# Main.net
KiCad netlist of a schematic drawn in Altium Designer
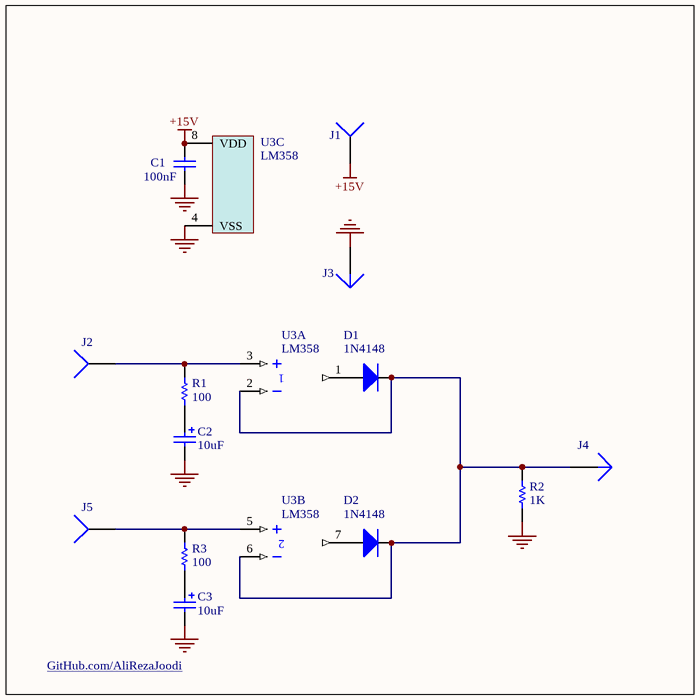
[diagram p0: Main.SchDoc]

(export (version "E")
  (design (tool "Eeschema 10.0.6"))
  (components
    (comp (ref "C1")
      (value "100nF")
      (footprint "CAPNTO2.54-3.05x1.78A")
      (description "Capacitor")
      (fields (field (name "MANUFACTURER") "Generic Components") (field (name "PUBLISHER") "Altium Limited"))
      (libsource (lib "Miscellaneous Devices") (part "Cap"))
    )
    (comp (ref "C2")
      (value "10uF")
      (footprint "CAPPR2.5-5x6")
      (description "Polarized Capacitor (Radial)")
      (fields (field (name "MANUFACTURER") "Generic Components") (field (name "PUBLISHER") "Altium Limited"))
      (libsource (lib "Miscellaneous Devices") (part "Cap Pol1"))
    )
    (comp (ref "C3")
      (value "10uF")
      (footprint "CAPPR2.5-5x6")
      (description "Polarized Capacitor (Radial)")
      (fields (field (name "MANUFACTURER") "Generic Components") (field (name "PUBLISHER") "Altium Limited"))
      (libsource (lib "Miscellaneous Devices") (part "Cap Pol1"))
    )
    (comp (ref "D1")
      (value "1N4148")
      (footprint "DIODE0.4_Glass")
      (description "Default Diode")
      (fields (field (name "MANUFACTURER") "Generic Components") (field (name "PUBLISHER") "Altium Limited"))
      (libsource (lib "Miscellaneous Devices") (part "Diode"))
    )
    (comp (ref "D2")
      (value "1N4148")
      (footprint "DIODE0.4_Glass")
      (description "Default Diode")
      (fields (field (name "MANUFACTURER") "Generic Components") (field (name "PUBLISHER") "Altium Limited"))
      (libsource (lib "Miscellaneous Devices") (part "Diode"))
    )
    (comp (ref "J1")
      (value "COAX-F")
      (footprint "PIN1")
      (description "Coax-F Connector")
      (fields (field (name "MANUFACTURER") "Generic Components") (field (name "PUBLISHER") "Altium Limited"))
      (libsource (lib "Miscellaneous Connectors") (part "COAX-F"))
    )
    (comp (ref "J2")
      (value "COAX-F")
      (footprint "PIN1")
      (description "Coax-F Connector")
      (fields (field (name "MANUFACTURER") "Generic Components") (field (name "PUBLISHER") "Altium Limited"))
      (libsource (lib "Miscellaneous Connectors") (part "COAX-F"))
    )
    (comp (ref "J3")
      (value "COAX-M")
      (footprint "PIN1")
      (description "Coax-M Connector")
      (fields (field (name "MANUFACTURER") "Generic Components") (field (name "PUBLISHER") "Altium Limited"))
      (libsource (lib "Miscellaneous Connectors") (part "COAX-M"))
    )
    (comp (ref "J4")
      (value "COAX-M")
      (footprint "PIN1")
      (description "Coax-M Connector")
      (fields (field (name "MANUFACTURER") "Generic Components") (field (name "PUBLISHER") "Altium Limited"))
      (libsource (lib "Miscellaneous Connectors") (part "COAX-M"))
    )
    (comp (ref "J5")
      (value "COAX-F")
      (footprint "PIN1")
      (description "Coax-F Connector")
      (fields (field (name "MANUFACTURER") "Generic Components") (field (name "PUBLISHER") "Altium Limited"))
      (libsource (lib "Miscellaneous Connectors") (part "COAX-F"))
    )
    (comp (ref "R1")
      (value "100")
      (footprint "AXIAL-0.4")
      (description "Resistor")
      (fields (field (name "PUBLISHER") "Altium Limited"))
      (libsource (lib "Miscellaneous Devices") (part "Res1"))
    )
    (comp (ref "R2")
      (value "1K")
      (footprint "AXIAL-0.4")
      (description "Resistor")
      (fields (field (name "PUBLISHER") "Altium Limited"))
      (libsource (lib "Miscellaneous Devices") (part "Res1"))
    )
    (comp (ref "R3")
      (value "100")
      (footprint "AXIAL-0.4")
      (description "Resistor")
      (fields (field (name "PUBLISHER") "Altium Limited"))
      (libsource (lib "Miscellaneous Devices") (part "Res1"))
    )
    (comp (ref "U3")
      (value "LM358")
      (footprint "DIP8")
      (description "Dual Low-Power Operational Amplifier")
      (fields (field (name "PUBLISHER") "Altium Limited"))
      (libsource (lib "my Libraries") (part "LM358"))
    )
  )
  (nets
    (net (code "1") (name "+15V") (class "Default")
      (node (ref "C1") (pin "2") (pinfunction "2_2") (pintype "passive"))
      (node (ref "J1") (pin "1") (pinfunction "A_1") (pintype "passive"))
      (node (ref "U3") (pin "8") (pinfunction "VDD_8") (pintype "passive"))
    )
    (net (code "2") (name "GND") (class "Default")
      (node (ref "C1") (pin "1") (pinfunction "1_1") (pintype "passive"))
      (node (ref "C2") (pin "2") (pinfunction "2_2") (pintype "passive"))
      (node (ref "C3") (pin "2") (pinfunction "2_2") (pintype "passive"))
      (node (ref "J3") (pin "1") (pinfunction "A_1") (pintype "passive"))
      (node (ref "R2") (pin "2") (pinfunction "2_2") (pintype "passive"))
      (node (ref "U3") (pin "4") (pinfunction "VSS_4") (pintype "power_in"))
    )
    (net (code "3") (name "Net-(C2-Pad1)") (class "Default")
      (node (ref "C2") (pin "1") (pinfunction "1_1") (pintype "passive"))
      (node (ref "R1") (pin "2") (pinfunction "2_2") (pintype "passive"))
    )
    (net (code "4") (name "Net-(C3-Pad1)") (class "Default")
      (node (ref "C3") (pin "1") (pinfunction "1_1") (pintype "passive"))
      (node (ref "R3") (pin "2") (pinfunction "2_2") (pintype "passive"))
    )
    (net (code "5") (name "Net-(D1-A)") (class "Default")
      (node (ref "D1") (pin "1") (pinfunction "A_1") (pintype "passive"))
      (node (ref "U3") (pin "1") (pinfunction "OUT_1") (pintype "output"))
    )
    (net (code "6") (name "Net-(D1-K)") (class "Default")
      (node (ref "D1") (pin "2") (pinfunction "K_2") (pintype "passive"))
      (node (ref "D2") (pin "2") (pinfunction "K_2") (pintype "passive"))
      (node (ref "J4") (pin "1") (pinfunction "A_1") (pintype "passive"))
      (node (ref "R2") (pin "1") (pinfunction "1_1") (pintype "passive"))
      (node (ref "U3") (pin "2") (pinfunction "IN-_2") (pintype "input"))
      (node (ref "U3") (pin "6") (pinfunction "IN-_6") (pintype "input"))
    )
    (net (code "7") (name "Net-(D2-A)") (class "Default")
      (node (ref "D2") (pin "1") (pinfunction "A_1") (pintype "passive"))
      (node (ref "U3") (pin "7") (pinfunction "OUT_7") (pintype "output"))
    )
    (net (code "8") (name "Net-(J2-A)") (class "Default")
      (node (ref "J2") (pin "1") (pinfunction "A_1") (pintype "passive"))
      (node (ref "R1") (pin "1") (pinfunction "1_1") (pintype "passive"))
      (node (ref "U3") (pin "3") (pinfunction "IN+_3") (pintype "input"))
    )
    (net (code "9") (name "Net-(J5-A)") (class "Default")
      (node (ref "J5") (pin "1") (pinfunction "A_1") (pintype "passive"))
      (node (ref "R3") (pin "1") (pinfunction "1_1") (pintype "passive"))
      (node (ref "U3") (pin "5") (pinfunction "IN+_5") (pintype "input"))
    )
  )
)
